# Condor2a_Power_Module.net
KiCad netlist of a schematic drawn in Altium Designer
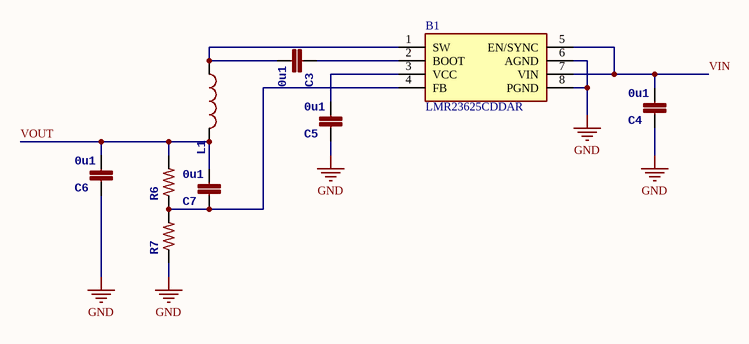
[diagram p0: Condor2a_Power_Module.SchDoc]

(export (version "E")
  (design (tool "Eeschema 10.0.6"))
  (components
    (comp (ref "B1")
      (value "LMR23625CDDAR")
      (footprint "SOT127P600X170-8N")
      (description "SIMPLE SWITCHER, 36V 2.5A Synchronous Step-Down Converter")
      (fields (field (name "MOUSER PART NUMBER") "595-LMR23625CDDAR"))
      (libsource (lib "CB_REV_C") (part "LMR23625CDDAR"))
    )
    (comp (ref "C3")
      (value "0u1")
      (footprint "0402-CAP")
      (fields (field (name "PARTNO") "CC0402ZRY5V7BB104"))
      (libsource (lib "") (part "CAP0402_1"))
    )
    (comp (ref "C4")
      (value "0u1")
      (footprint "0402-CAP")
      (fields (field (name "PARTNO") "CC0402ZRY5V7BB104"))
      (libsource (lib "CB_REV_C") (part "CAP0402"))
    )
    (comp (ref "C5")
      (value "0u1")
      (footprint "0402-CAP")
      (fields (field (name "PARTNO") "CC0402ZRY5V7BB104"))
      (libsource (lib "CB_REV_C") (part "CAP0402"))
    )
    (comp (ref "C6")
      (value "0u1")
      (footprint "0402-CAP")
      (fields (field (name "PARTNO") "CC0402ZRY5V7BB104"))
      (libsource (lib "CB_REV_C") (part "CAP0402"))
    )
    (comp (ref "C7")
      (value "0u1")
      (footprint "0402-CAP")
      (fields (field (name "PARTNO") "CC0402ZRY5V7BB104"))
      (libsource (lib "CB_REV_C") (part "CAP0402"))
    )
    (comp (ref "L1")
      (value "INDUCTOR0805")
      (footprint "0805-IND")
      (libsource (lib "CB_REV_C") (part "INDUCTOR0805"))
    )
    (comp (ref "R6")
      (value "RESISTOR0402-RES")
      (footprint "0402-RES")
      (libsource (lib "CB_REV_C") (part "RESISTOR0402-RES"))
    )
    (comp (ref "R7")
      (value "RESISTOR0402-RES")
      (footprint "0402-RES")
      (libsource (lib "CB_REV_C") (part "RESISTOR0402-RES"))
    )
  )
  (nets
    (net (code "1") (name "/VIN") (class "Default")
      (node (ref "B1") (pin "5") (pinfunction "EN/SYNC_5") (pintype "passive"))
      (node (ref "B1") (pin "7") (pinfunction "VIN_7") (pintype "passive"))
      (node (ref "C4") (pin "P$1") (pinfunction "1_P$1") (pintype "passive"))
    )
    (net (code "2") (name "/VOUT") (class "Default")
      (node (ref "C6") (pin "P$1") (pinfunction "1_P$1") (pintype "passive"))
      (node (ref "C7") (pin "P$1") (pinfunction "1_P$1") (pintype "passive"))
      (node (ref "L1") (pin "P$2") (pinfunction "2_P$2") (pintype "passive"))
      (node (ref "R6") (pin "P2") (pinfunction "2_P2") (pintype "passive"))
    )
    (net (code "3") (name "GND") (class "Default")
      (node (ref "B1") (pin "6") (pinfunction "AGND_6") (pintype "passive"))
      (node (ref "B1") (pin "8") (pinfunction "PGND_8") (pintype "passive"))
      (node (ref "C4") (pin "P$2") (pinfunction "2_P$2") (pintype "passive"))
      (node (ref "C5") (pin "P$2") (pinfunction "2_P$2") (pintype "passive"))
      (node (ref "C6") (pin "P$2") (pinfunction "2_P$2") (pintype "passive"))
      (node (ref "R7") (pin "P1") (pinfunction "1_P1") (pintype "passive"))
    )
    (net (code "4") (name "Net-(B1-BOOT)") (class "Default")
      (node (ref "B1") (pin "2") (pinfunction "BOOT_2") (pintype "passive"))
      (node (ref "C3") (pin "P$2") (pinfunction "2_P$2") (pintype "passive"))
    )
    (net (code "5") (name "Net-(B1-FB)") (class "Default")
      (node (ref "B1") (pin "4") (pinfunction "FB_4") (pintype "passive"))
      (node (ref "C7") (pin "P$2") (pinfunction "2_P$2") (pintype "passive"))
      (node (ref "R6") (pin "P1") (pinfunction "1_P1") (pintype "passive"))
      (node (ref "R7") (pin "P2") (pinfunction "2_P2") (pintype "passive"))
    )
    (net (code "6") (name "Net-(B1-SW)") (class "Default")
      (node (ref "B1") (pin "1") (pinfunction "SW_1") (pintype "passive"))
      (node (ref "C3") (pin "P$1") (pinfunction "1_P$1") (pintype "passive"))
      (node (ref "L1") (pin "P$1") (pinfunction "1_P$1") (pintype "passive"))
    )
    (net (code "7") (name "Net-(B1-VCC)") (class "Default")
      (node (ref "B1") (pin "3") (pinfunction "VCC_3") (pintype "passive"))
      (node (ref "C5") (pin "P$1") (pinfunction "1_P$1") (pintype "passive"))
    )
  )
)
